# ProDocument_N64_SpyDVI_QSB_2024-08-22.net
KiCad netlist of a schematic drawn in EasyEDA Pro
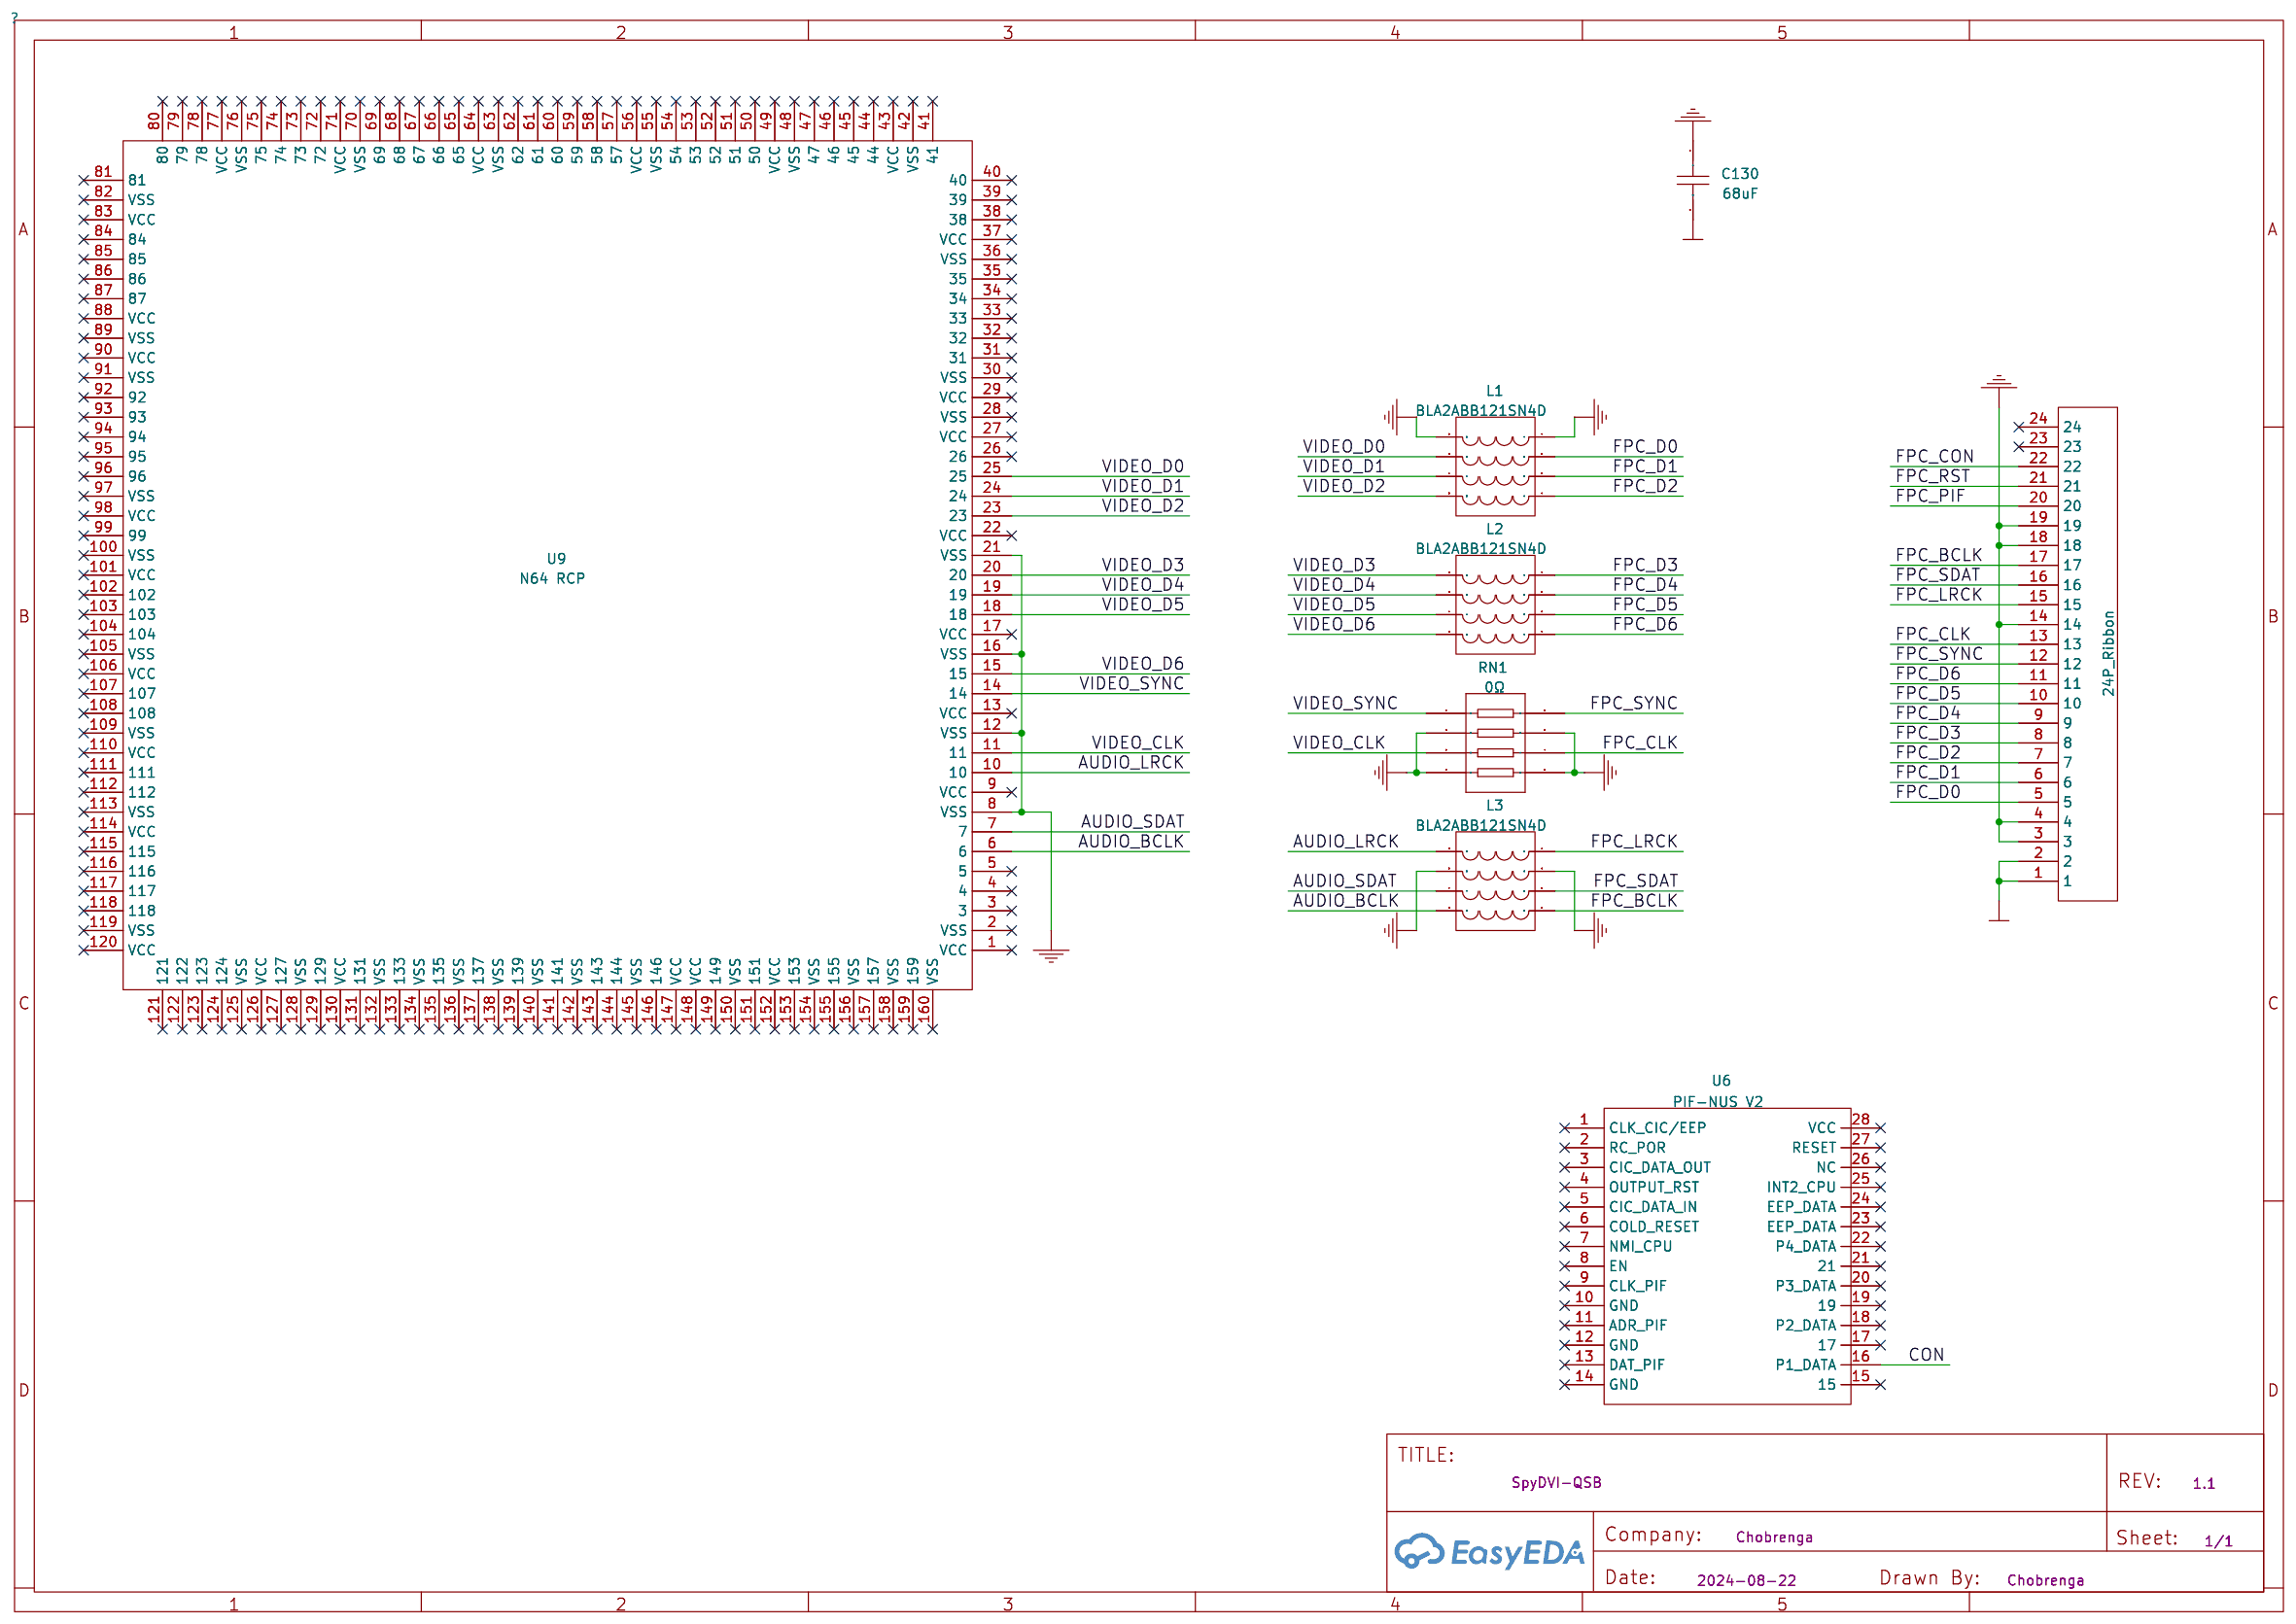
[diagram p0: schematic sheet]

(export (version "E")
  (design (tool "Eeschema 10.0.6"))
  (components
    (comp (ref "C130") (value "68uF") (libsource (lib "easyedapro") (part "68uF")))
    (comp (ref "L1")
      (value "BLA2ABB121SN4D")
      (footprint "easyedapro:BEAD-SMD_8P-L2.0-W1.0-P0.50-TL")
      (fields (field (name "Manufacturer") "muRata(村田)"))
      (libsource (lib "easyedapro") (part "BLA2ABB121SN4D"))
    )
    (comp (ref "L2")
      (value "BLA2ABB121SN4D")
      (footprint "easyedapro:BEAD-SMD_8P-L2.0-W1.0-P0.50-TL")
      (fields (field (name "Manufacturer") "muRata(村田)"))
      (libsource (lib "easyedapro") (part "BLA2ABB121SN4D"))
    )
    (comp (ref "L3")
      (value "BLA2ABB121SN4D")
      (footprint "easyedapro:BEAD-SMD_8P-L2.0-W1.0-P0.50-TL")
      (fields (field (name "Manufacturer") "muRata(村田)"))
      (libsource (lib "easyedapro") (part "BLA2ABB121SN4D"))
    )
    (comp (ref "RN1")
      (value "0Ω")
      (footprint "easyedapro:RES-ARRAY-SMD_0402-8P-L2.0-W1.0-BL")
      (fields (field (name "Manufacturer Part") "RC-MT08W000JT") (field (name "Manufacturer") "FH(风华)"))
      (libsource (lib "easyedapro") (part "0Ω"))
    )
    (comp (ref "U1")
      (value "24P_Ribbon")
      (footprint "easyedapro:24P_FFC")
      (libsource (lib "easyedapro") (part "24P_Ribbon"))
    )
    (comp (ref "U6") (value "PIF-NUS V2") (libsource (lib "easyedapro") (part "PIF-NUS V2")))
    (comp (ref "U9")
      (value "N64 RCP")
      (footprint "easyedapro:RCP NUS")
      (libsource (lib "easyedapro") (part "N64 RCP"))
    )
  )
  (nets
    (net (code "1") (name "+5V") (class "Default")
      (node (ref "C130") (pin "2") (pinfunction "2_2") (pintype "unspecified"))
      (node (ref "U1") (pin "1") (pinfunction "1_1") (pintype "unspecified"))
      (node (ref "U1") (pin "2") (pinfunction "2_2") (pintype "unspecified"))
    )
    (net (code "2") (name "/AUDIO_BCLK") (class "Default")
      (node (ref "L3") (pin "8") (pinfunction "8_8") (pintype "unspecified"))
      (node (ref "U9") (pin "6") (pinfunction "6_6") (pintype "unspecified"))
    )
    (net (code "3") (name "/AUDIO_LRCK") (class "Default")
      (node (ref "L3") (pin "5") (pinfunction "5_5") (pintype "unspecified"))
      (node (ref "U9") (pin "10") (pinfunction "10_10") (pintype "unspecified"))
    )
    (net (code "4") (name "/AUDIO_SDAT") (class "Default")
      (node (ref "L3") (pin "7") (pinfunction "7_7") (pintype "unspecified"))
      (node (ref "U9") (pin "7") (pinfunction "7_7") (pintype "unspecified"))
    )
    (net (code "5") (name "/CON") (class "Default")
      (node (ref "U6") (pin "16") (pinfunction "P1_DATA_16") (pintype "unspecified"))
    )
    (net (code "6") (name "/FPC_BCLK") (class "Default")
      (node (ref "L3") (pin "1") (pinfunction "1_1") (pintype "unspecified"))
      (node (ref "U1") (pin "17") (pinfunction "17_17") (pintype "unspecified"))
    )
    (net (code "7") (name "/FPC_CLK") (class "Default")
      (node (ref "RN1") (pin "7") (pinfunction "7_7") (pintype "input"))
      (node (ref "U1") (pin "13") (pinfunction "13_13") (pintype "unspecified"))
    )
    (net (code "8") (name "/FPC_CON") (class "Default")
      (node (ref "U1") (pin "22") (pinfunction "22_22") (pintype "unspecified"))
    )
    (net (code "9") (name "/FPC_D0") (class "Default")
      (node (ref "L1") (pin "3") (pinfunction "3_3") (pintype "unspecified"))
      (node (ref "U1") (pin "5") (pinfunction "5_5") (pintype "unspecified"))
    )
    (net (code "10") (name "/FPC_D1") (class "Default")
      (node (ref "L1") (pin "2") (pinfunction "2_2") (pintype "unspecified"))
      (node (ref "U1") (pin "6") (pinfunction "6_6") (pintype "unspecified"))
    )
    (net (code "11") (name "/FPC_D2") (class "Default")
      (node (ref "L1") (pin "1") (pinfunction "1_1") (pintype "unspecified"))
      (node (ref "U1") (pin "7") (pinfunction "7_7") (pintype "unspecified"))
    )
    (net (code "12") (name "/FPC_D3") (class "Default")
      (node (ref "L2") (pin "4") (pinfunction "4_4") (pintype "unspecified"))
      (node (ref "U1") (pin "8") (pinfunction "8_8") (pintype "unspecified"))
    )
    (net (code "13") (name "/FPC_D4") (class "Default")
      (node (ref "L2") (pin "3") (pinfunction "3_3") (pintype "unspecified"))
      (node (ref "U1") (pin "9") (pinfunction "9_9") (pintype "unspecified"))
    )
    (net (code "14") (name "/FPC_D5") (class "Default")
      (node (ref "L2") (pin "2") (pinfunction "2_2") (pintype "unspecified"))
      (node (ref "U1") (pin "10") (pinfunction "10_10") (pintype "unspecified"))
    )
    (net (code "15") (name "/FPC_D6") (class "Default")
      (node (ref "L2") (pin "1") (pinfunction "1_1") (pintype "unspecified"))
      (node (ref "U1") (pin "11") (pinfunction "11_11") (pintype "unspecified"))
    )
    (net (code "16") (name "/FPC_LRCK") (class "Default")
      (node (ref "L3") (pin "4") (pinfunction "4_4") (pintype "unspecified"))
      (node (ref "U1") (pin "15") (pinfunction "15_15") (pintype "unspecified"))
    )
    (net (code "17") (name "/FPC_PIF") (class "Default")
      (node (ref "U1") (pin "20") (pinfunction "20_20") (pintype "unspecified"))
    )
    (net (code "18") (name "/FPC_RST") (class "Default")
      (node (ref "U1") (pin "21") (pinfunction "21_21") (pintype "unspecified"))
    )
    (net (code "19") (name "/FPC_SDAT") (class "Default")
      (node (ref "L3") (pin "2") (pinfunction "2_2") (pintype "unspecified"))
      (node (ref "U1") (pin "16") (pinfunction "16_16") (pintype "unspecified"))
    )
    (net (code "20") (name "/FPC_SYNC") (class "Default")
      (node (ref "RN1") (pin "5") (pinfunction "5_5") (pintype "input"))
      (node (ref "U1") (pin "12") (pinfunction "12_12") (pintype "unspecified"))
    )
    (net (code "21") (name "/VIDEO_CLK") (class "Default")
      (node (ref "RN1") (pin "2") (pinfunction "2_2") (pintype "input"))
      (node (ref "U9") (pin "11") (pinfunction "11_11") (pintype "unspecified"))
    )
    (net (code "22") (name "/VIDEO_D0") (class "Default")
      (node (ref "L1") (pin "6") (pinfunction "6_6") (pintype "unspecified"))
      (node (ref "U9") (pin "25") (pinfunction "25_25") (pintype "unspecified"))
    )
    (net (code "23") (name "/VIDEO_D1") (class "Default")
      (node (ref "L1") (pin "7") (pinfunction "7_7") (pintype "unspecified"))
      (node (ref "U9") (pin "24") (pinfunction "24_24") (pintype "unspecified"))
    )
    (net (code "24") (name "/VIDEO_D2") (class "Default")
      (node (ref "L1") (pin "8") (pinfunction "8_8") (pintype "unspecified"))
      (node (ref "U9") (pin "23") (pinfunction "23_23") (pintype "unspecified"))
    )
    (net (code "25") (name "/VIDEO_D3") (class "Default")
      (node (ref "L2") (pin "5") (pinfunction "5_5") (pintype "unspecified"))
      (node (ref "U9") (pin "20") (pinfunction "20_20") (pintype "unspecified"))
    )
    (net (code "26") (name "/VIDEO_D4") (class "Default")
      (node (ref "L2") (pin "6") (pinfunction "6_6") (pintype "unspecified"))
      (node (ref "U9") (pin "19") (pinfunction "19_19") (pintype "unspecified"))
    )
    (net (code "27") (name "/VIDEO_D5") (class "Default")
      (node (ref "L2") (pin "7") (pinfunction "7_7") (pintype "unspecified"))
      (node (ref "U9") (pin "18") (pinfunction "18_18") (pintype "unspecified"))
    )
    (net (code "28") (name "/VIDEO_D6") (class "Default")
      (node (ref "L2") (pin "8") (pinfunction "8_8") (pintype "unspecified"))
      (node (ref "U9") (pin "15") (pinfunction "15_15") (pintype "unspecified"))
    )
    (net (code "29") (name "/VIDEO_SYNC") (class "Default")
      (node (ref "RN1") (pin "4") (pinfunction "4_4") (pintype "input"))
      (node (ref "U9") (pin "14") (pinfunction "14_14") (pintype "unspecified"))
    )
    (net (code "30") (name "GND") (class "Default")
      (node (ref "C130") (pin "1") (pinfunction "1_1") (pintype "unspecified"))
      (node (ref "L1") (pin "4") (pinfunction "4_4") (pintype "unspecified"))
      (node (ref "L1") (pin "5") (pinfunction "5_5") (pintype "unspecified"))
      (node (ref "L3") (pin "3") (pinfunction "3_3") (pintype "unspecified"))
      (node (ref "L3") (pin "6") (pinfunction "6_6") (pintype "unspecified"))
      (node (ref "RN1") (pin "1") (pinfunction "1_1") (pintype "input"))
      (node (ref "RN1") (pin "3") (pinfunction "3_3") (pintype "input"))
      (node (ref "RN1") (pin "6") (pinfunction "6_6") (pintype "input"))
      (node (ref "RN1") (pin "8") (pinfunction "8_8") (pintype "input"))
      (node (ref "U1") (pin "14") (pinfunction "14_14") (pintype "unspecified"))
      (node (ref "U1") (pin "18") (pinfunction "18_18") (pintype "unspecified"))
      (node (ref "U1") (pin "19") (pinfunction "19_19") (pintype "unspecified"))
      (node (ref "U1") (pin "3") (pinfunction "3_3") (pintype "unspecified"))
      (node (ref "U1") (pin "4") (pinfunction "4_4") (pintype "unspecified"))
      (node (ref "U9") (pin "12") (pinfunction "VSS_12") (pintype "unspecified"))
      (node (ref "U9") (pin "16") (pinfunction "VSS_16") (pintype "unspecified"))
      (node (ref "U9") (pin "21") (pinfunction "VSS_21") (pintype "unspecified"))
      (node (ref "U9") (pin "8") (pinfunction "VSS_8") (pintype "unspecified"))
    )
    (net (code "31") (name "unconnected-(U1-Pad23)") (class "Default")
      (node (ref "U1") (pin "23") (pinfunction "23_23") (pintype "unspecified+no_connect"))
    )
    (net (code "32") (name "unconnected-(U1-Pad24)") (class "Default")
      (node (ref "U1") (pin "24") (pinfunction "24_24") (pintype "unspecified+no_connect"))
    )
    (net (code "33") (name "unconnected-(U6-ADR_PIF-Pad11)") (class "Default")
      (node (ref "U6") (pin "11") (pinfunction "ADR_PIF_11") (pintype "unspecified+no_connect"))
    )
    (net (code "34") (name "unconnected-(U6-CIC_DATA_IN-Pad5)") (class "Default")
      (node (ref "U6") (pin "5") (pinfunction "CIC_DATA_IN_5") (pintype "unspecified+no_connect"))
    )
    (net (code "35") (name "unconnected-(U6-CIC_DATA_OUT-Pad3)") (class "Default")
      (node (ref "U6") (pin "3") (pinfunction "CIC_DATA_OUT_3") (pintype "unspecified+no_connect"))
    )
    (net (code "36") (name "unconnected-(U6-CLK_CIC{slash}EEP-Pad1)") (class "Default")
      (node (ref "U6") (pin "1") (pinfunction "CLK_CIC/EEP_1") (pintype "unspecified+no_connect"))
    )
    (net (code "37") (name "unconnected-(U6-CLK_PIF-Pad9)") (class "Default")
      (node (ref "U6") (pin "9") (pinfunction "CLK_PIF_9") (pintype "unspecified+no_connect"))
    )
    (net (code "38") (name "unconnected-(U6-COLD_RESET-Pad6)") (class "Default")
      (node (ref "U6") (pin "6") (pinfunction "COLD_RESET_6") (pintype "unspecified+no_connect"))
    )
    (net (code "39") (name "unconnected-(U6-DAT_PIF-Pad13)") (class "Default")
      (node (ref "U6") (pin "13") (pinfunction "DAT_PIF_13") (pintype "unspecified+no_connect"))
    )
    (net (code "40") (name "unconnected-(U6-EEP_DATA-Pad23)") (class "Default")
      (node (ref "U6") (pin "23") (pinfunction "EEP_DATA_23") (pintype "unspecified+no_connect"))
    )
    (net (code "41") (name "unconnected-(U6-EEP_DATA-Pad24)") (class "Default")
      (node (ref "U6") (pin "24") (pinfunction "EEP_DATA_24") (pintype "unspecified+no_connect"))
    )
    (net (code "42") (name "unconnected-(U6-EN-Pad8)") (class "Default")
      (node (ref "U6") (pin "8") (pinfunction "EN_8") (pintype "unspecified+no_connect"))
    )
    (net (code "43") (name "unconnected-(U6-GND-Pad10)") (class "Default")
      (node (ref "U6") (pin "10") (pinfunction "GND_10") (pintype "unspecified+no_connect"))
    )
    (net (code "44") (name "unconnected-(U6-GND-Pad12)") (class "Default")
      (node (ref "U6") (pin "12") (pinfunction "GND_12") (pintype "unspecified+no_connect"))
    )
    (net (code "45") (name "unconnected-(U6-GND-Pad14)") (class "Default")
      (node (ref "U6") (pin "14") (pinfunction "GND_14") (pintype "unspecified+no_connect"))
    )
    (net (code "46") (name "unconnected-(U6-INT2_CPU-Pad25)") (class "Default")
      (node (ref "U6") (pin "25") (pinfunction "INT2_CPU_25") (pintype "unspecified+no_connect"))
    )
    (net (code "47") (name "unconnected-(U6-NC-Pad26)") (class "Default")
      (node (ref "U6") (pin "26") (pinfunction "NC_26") (pintype "unspecified+no_connect"))
    )
    (net (code "48") (name "unconnected-(U6-NMI_CPU-Pad7)") (class "Default")
      (node (ref "U6") (pin "7") (pinfunction "NMI_CPU_7") (pintype "unspecified+no_connect"))
    )
    (net (code "49") (name "unconnected-(U6-OUTPUT_RST-Pad4)") (class "Default")
      (node (ref "U6") (pin "4") (pinfunction "OUTPUT_RST_4") (pintype "unspecified+no_connect"))
    )
    (net (code "50") (name "unconnected-(U6-P2_DATA-Pad18)") (class "Default")
      (node (ref "U6") (pin "18") (pinfunction "P2_DATA_18") (pintype "unspecified+no_connect"))
    )
    (net (code "51") (name "unconnected-(U6-P3_DATA-Pad20)") (class "Default")
      (node (ref "U6") (pin "20") (pinfunction "P3_DATA_20") (pintype "unspecified+no_connect"))
    )
    (net (code "52") (name "unconnected-(U6-P4_DATA-Pad22)") (class "Default")
      (node (ref "U6") (pin "22") (pinfunction "P4_DATA_22") (pintype "unspecified+no_connect"))
    )
    (net (code "53") (name "unconnected-(U6-Pad15)") (class "Default")
      (node (ref "U6") (pin "15") (pinfunction "15_15") (pintype "unspecified+no_connect"))
    )
    (net (code "54") (name "unconnected-(U6-Pad17)") (class "Default")
      (node (ref "U6") (pin "17") (pinfunction "17_17") (pintype "unspecified+no_connect"))
    )
    (net (code "55") (name "unconnected-(U6-Pad19)") (class "Default")
      (node (ref "U6") (pin "19") (pinfunction "19_19") (pintype "unspecified+no_connect"))
    )
    (net (code "56") (name "unconnected-(U6-Pad21)") (class "Default")
      (node (ref "U6") (pin "21") (pinfunction "21_21") (pintype "unspecified+no_connect"))
    )
    (net (code "57") (name "unconnected-(U6-RC_POR-Pad2)") (class "Default")
      (node (ref "U6") (pin "2") (pinfunction "RC_POR_2") (pintype "unspecified+no_connect"))
    )
    (net (code "58") (name "unconnected-(U6-RESET-Pad27)") (class "Default")
      (node (ref "U6") (pin "27") (pinfunction "RESET_27") (pintype "unspecified+no_connect"))
    )
    (net (code "59") (name "unconnected-(U6-VCC-Pad28)") (class "Default")
      (node (ref "U6") (pin "28") (pinfunction "VCC_28") (pintype "unspecified+no_connect"))
    )
    (net (code "60") (name "unconnected-(U9-Pad3)") (class "Default")
      (node (ref "U9") (pin "3") (pinfunction "3_3") (pintype "unspecified+no_connect"))
    )
    (net (code "61") (name "unconnected-(U9-Pad4)") (class "Default")
      (node (ref "U9") (pin "4") (pinfunction "4_4") (pintype "unspecified+no_connect"))
    )
    (net (code "62") (name "unconnected-(U9-Pad5)") (class "Default")
      (node (ref "U9") (pin "5") (pinfunction "5_5") (pintype "unspecified+no_connect"))
    )
    (net (code "63") (name "unconnected-(U9-Pad26)") (class "Default")
      (node (ref "U9") (pin "26") (pinfunction "26_26") (pintype "unspecified+no_connect"))
    )
    (net (code "64") (name "unconnected-(U9-Pad31)") (class "Default")
      (node (ref "U9") (pin "31") (pinfunction "31_31") (pintype "unspecified+no_connect"))
    )
    (net (code "65") (name "unconnected-(U9-Pad32)") (class "Default")
      (node (ref "U9") (pin "32") (pinfunction "32_32") (pintype "unspecified+no_connect"))
    )
    (net (code "66") (name "unconnected-(U9-Pad33)") (class "Default")
      (node (ref "U9") (pin "33") (pinfunction "33_33") (pintype "unspecified+no_connect"))
    )
    (net (code "67") (name "unconnected-(U9-Pad34)") (class "Default")
      (node (ref "U9") (pin "34") (pinfunction "34_34") (pintype "unspecified+no_connect"))
    )
    (net (code "68") (name "unconnected-(U9-Pad35)") (class "Default")
      (node (ref "U9") (pin "35") (pinfunction "35_35") (pintype "unspecified+no_connect"))
    )
    (net (code "69") (name "unconnected-(U9-Pad38)") (class "Default")
      (node (ref "U9") (pin "38") (pinfunction "38_38") (pintype "unspecified+no_connect"))
    )
    (net (code "70") (name "unconnected-(U9-Pad39)") (class "Default")
      (node (ref "U9") (pin "39") (pinfunction "39_39") (pintype "unspecified+no_connect"))
    )
    (net (code "71") (name "unconnected-(U9-Pad40)") (class "Default")
      (node (ref "U9") (pin "40") (pinfunction "40_40") (pintype "unspecified+no_connect"))
    )
    (net (code "72") (name "unconnected-(U9-Pad41)") (class "Default")
      (node (ref "U9") (pin "41") (pinfunction "41_41") (pintype "unspecified+no_connect"))
    )
    (net (code "73") (name "unconnected-(U9-Pad44)") (class "Default")
      (node (ref "U9") (pin "44") (pinfunction "44_44") (pintype "unspecified+no_connect"))
    )
    (net (code "74") (name "unconnected-(U9-Pad45)") (class "Default")
      (node (ref "U9") (pin "45") (pinfunction "45_45") (pintype "unspecified+no_connect"))
    )
    (net (code "75") (name "unconnected-(U9-Pad46)") (class "Default")
      (node (ref "U9") (pin "46") (pinfunction "46_46") (pintype "unspecified+no_connect"))
    )
    (net (code "76") (name "unconnected-(U9-Pad47)") (class "Default")
      (node (ref "U9") (pin "47") (pinfunction "47_47") (pintype "unspecified+no_connect"))
    )
    (net (code "77") (name "unconnected-(U9-Pad50)") (class "Default")
      (node (ref "U9") (pin "50") (pinfunction "50_50") (pintype "unspecified+no_connect"))
    )
    (net (code "78") (name "unconnected-(U9-Pad51)") (class "Default")
      (node (ref "U9") (pin "51") (pinfunction "51_51") (pintype "unspecified+no_connect"))
    )
    (net (code "79") (name "unconnected-(U9-Pad52)") (class "Default")
      (node (ref "U9") (pin "52") (pinfunction "52_52") (pintype "unspecified+no_connect"))
    )
    (net (code "80") (name "unconnected-(U9-Pad53)") (class "Default")
      (node (ref "U9") (pin "53") (pinfunction "53_53") (pintype "unspecified+no_connect"))
    )
    (net (code "81") (name "unconnected-(U9-Pad54)") (class "Default")
      (node (ref "U9") (pin "54") (pinfunction "54_54") (pintype "unspecified+no_connect"))
    )
    (net (code "82") (name "unconnected-(U9-Pad57)") (class "Default")
      (node (ref "U9") (pin "57") (pinfunction "57_57") (pintype "unspecified+no_connect"))
    )
    (net (code "83") (name "unconnected-(U9-Pad58)") (class "Default")
      (node (ref "U9") (pin "58") (pinfunction "58_58") (pintype "unspecified+no_connect"))
    )
    (net (code "84") (name "unconnected-(U9-Pad59)") (class "Default")
      (node (ref "U9") (pin "59") (pinfunction "59_59") (pintype "unspecified+no_connect"))
    )
    (net (code "85") (name "unconnected-(U9-Pad60)") (class "Default")
      (node (ref "U9") (pin "60") (pinfunction "60_60") (pintype "unspecified+no_connect"))
    )
    (net (code "86") (name "unconnected-(U9-Pad61)") (class "Default")
      (node (ref "U9") (pin "61") (pinfunction "61_61") (pintype "unspecified+no_connect"))
    )
    (net (code "87") (name "unconnected-(U9-Pad62)") (class "Default")
      (node (ref "U9") (pin "62") (pinfunction "62_62") (pintype "unspecified+no_connect"))
    )
    (net (code "88") (name "unconnected-(U9-Pad65)") (class "Default")
      (node (ref "U9") (pin "65") (pinfunction "65_65") (pintype "unspecified+no_connect"))
    )
    (net (code "89") (name "unconnected-(U9-Pad66)") (class "Default")
      (node (ref "U9") (pin "66") (pinfunction "66_66") (pintype "unspecified+no_connect"))
    )
    (net (code "90") (name "unconnected-(U9-Pad67)") (class "Default")
      (node (ref "U9") (pin "67") (pinfunction "67_67") (pintype "unspecified+no_connect"))
    )
    (net (code "91") (name "unconnected-(U9-Pad68)") (class "Default")
      (node (ref "U9") (pin "68") (pinfunction "68_68") (pintype "unspecified+no_connect"))
    )
    (net (code "92") (name "unconnected-(U9-Pad69)") (class "Default")
      (node (ref "U9") (pin "69") (pinfunction "69_69") (pintype "unspecified+no_connect"))
    )
    (net (code "93") (name "unconnected-(U9-Pad72)") (class "Default")
      (node (ref "U9") (pin "72") (pinfunction "72_72") (pintype "unspecified+no_connect"))
    )
    (net (code "94") (name "unconnected-(U9-Pad73)") (class "Default")
      (node (ref "U9") (pin "73") (pinfunction "73_73") (pintype "unspecified+no_connect"))
    )
    (net (code "95") (name "unconnected-(U9-Pad74)") (class "Default")
      (node (ref "U9") (pin "74") (pinfunction "74_74") (pintype "unspecified+no_connect"))
    )
    (net (code "96") (name "unconnected-(U9-Pad75)") (class "Default")
      (node (ref "U9") (pin "75") (pinfunction "75_75") (pintype "unspecified+no_connect"))
    )
    (net (code "97") (name "unconnected-(U9-Pad78)") (class "Default")
      (node (ref "U9") (pin "78") (pinfunction "78_78") (pintype "unspecified+no_connect"))
    )
    (net (code "98") (name "unconnected-(U9-Pad79)") (class "Default")
      (node (ref "U9") (pin "79") (pinfunction "79_79") (pintype "unspecified+no_connect"))
    )
    (net (code "99") (name "unconnected-(U9-Pad80)") (class "Default")
      (node (ref "U9") (pin "80") (pinfunction "80_80") (pintype "unspecified+no_connect"))
    )
    (net (code "100") (name "unconnected-(U9-Pad81)") (class "Default")
      (node (ref "U9") (pin "81") (pinfunction "81_81") (pintype "unspecified+no_connect"))
    )
    (net (code "101") (name "unconnected-(U9-Pad84)") (class "Default")
      (node (ref "U9") (pin "84") (pinfunction "84_84") (pintype "unspecified+no_connect"))
    )
    (net (code "102") (name "unconnected-(U9-Pad85)") (class "Default")
      (node (ref "U9") (pin "85") (pinfunction "85_85") (pintype "unspecified+no_connect"))
    )
    (net (code "103") (name "unconnected-(U9-Pad86)") (class "Default")
      (node (ref "U9") (pin "86") (pinfunction "86_86") (pintype "unspecified+no_connect"))
    )
    (net (code "104") (name "unconnected-(U9-Pad87)") (class "Default")
      (node (ref "U9") (pin "87") (pinfunction "87_87") (pintype "unspecified+no_connect"))
    )
    (net (code "105") (name "unconnected-(U9-Pad92)") (class "Default")
      (node (ref "U9") (pin "92") (pinfunction "92_92") (pintype "unspecified+no_connect"))
    )
    (net (code "106") (name "unconnected-(U9-Pad93)") (class "Default")
      (node (ref "U9") (pin "93") (pinfunction "93_93") (pintype "unspecified+no_connect"))
    )
    (net (code "107") (name "unconnected-(U9-Pad94)") (class "Default")
      (node (ref "U9") (pin "94") (pinfunction "94_94") (pintype "unspecified+no_connect"))
    )
    (net (code "108") (name "unconnected-(U9-Pad95)") (class "Default")
      (node (ref "U9") (pin "95") (pinfunction "95_95") (pintype "unspecified+no_connect"))
    )
    (net (code "109") (name "unconnected-(U9-Pad96)") (class "Default")
      (node (ref "U9") (pin "96") (pinfunction "96_96") (pintype "unspecified+no_connect"))
    )
    (net (code "110") (name "unconnected-(U9-Pad99)") (class "Default")
      (node (ref "U9") (pin "99") (pinfunction "99_99") (pintype "unspecified+no_connect"))
    )
    (net (code "111") (name "unconnected-(U9-Pad102)") (class "Default")
      (node (ref "U9") (pin "102") (pinfunction "102_102") (pintype "unspecified+no_connect"))
    )
    (net (code "112") (name "unconnected-(U9-Pad103)") (class "Default")
      (node (ref "U9") (pin "103") (pinfunction "103_103") (pintype "unspecified+no_connect"))
    )
    (net (code "113") (name "unconnected-(U9-Pad104)") (class "Default")
      (node (ref "U9") (pin "104") (pinfunction "104_104") (pintype "unspecified+no_connect"))
    )
    (net (code "114") (name "unconnected-(U9-Pad107)") (class "Default")
      (node (ref "U9") (pin "107") (pinfunction "107_107") (pintype "unspecified+no_connect"))
    )
    (net (code "115") (name "unconnected-(U9-Pad108)") (class "Default")
      (node (ref "U9") (pin "108") (pinfunction "108_108") (pintype "unspecified+no_connect"))
    )
    (net (code "116") (name "unconnected-(U9-Pad111)") (class "Default")
      (node (ref "U9") (pin "111") (pinfunction "111_111") (pintype "unspecified+no_connect"))
    )
    (net (code "117") (name "unconnected-(U9-Pad112)") (class "Default")
      (node (ref "U9") (pin "112") (pinfunction "112_112") (pintype "unspecified+no_connect"))
    )
    (net (code "118") (name "unconnected-(U9-Pad115)") (class "Default")
      (node (ref "U9") (pin "115") (pinfunction "115_115") (pintype "unspecified+no_connect"))
    )
    (net (code "119") (name "unconnected-(U9-Pad116)") (class "Default")
      (node (ref "U9") (pin "116") (pinfunction "116_116") (pintype "unspecified+no_connect"))
    )
    (net (code "120") (name "unconnected-(U9-Pad117)") (class "Default")
      (node (ref "U9") (pin "117") (pinfunction "117_117") (pintype "unspecified+no_connect"))
    )
    (net (code "121") (name "unconnected-(U9-Pad118)") (class "Default")
      (node (ref "U9") (pin "118") (pinfunction "118_118") (pintype "unspecified+no_connect"))
    )
    (net (code "122") (name "unconnected-(U9-Pad121)") (class "Default")
      (node (ref "U9") (pin "121") (pinfunction "121_121") (pintype "unspecified+no_connect"))
    )
    (net (code "123") (name "unconnected-(U9-Pad122)") (class "Default")
      (node (ref "U9") (pin "122") (pinfunction "122_122") (pintype "unspecified+no_connect"))
    )
    (net (code "124") (name "unconnected-(U9-Pad123)") (class "Default")
      (node (ref "U9") (pin "123") (pinfunction "123_123") (pintype "unspecified+no_connect"))
    )
    (net (code "125") (name "unconnected-(U9-Pad124)") (class "Default")
      (node (ref "U9") (pin "124") (pinfunction "124_124") (pintype "unspecified+no_connect"))
    )
    (net (code "126") (name "unconnected-(U9-Pad127)") (class "Default")
      (node (ref "U9") (pin "127") (pinfunction "127_127") (pintype "unspecified+no_connect"))
    )
    (net (code "127") (name "unconnected-(U9-Pad129)") (class "Default")
      (node (ref "U9") (pin "129") (pinfunction "129_129") (pintype "unspecified+no_connect"))
    )
    (net (code "128") (name "unconnected-(U9-Pad131)") (class "Default")
      (node (ref "U9") (pin "131") (pinfunction "131_131") (pintype "unspecified+no_connect"))
    )
    (net (code "129") (name "unconnected-(U9-Pad133)") (class "Default")
      (node (ref "U9") (pin "133") (pinfunction "133_133") (pintype "unspecified+no_connect"))
    )
    (net (code "130") (name "unconnected-(U9-Pad135)") (class "Default")
      (node (ref "U9") (pin "135") (pinfunction "135_135") (pintype "unspecified+no_connect"))
    )
    (net (code "131") (name "unconnected-(U9-Pad137)") (class "Default")
      (node (ref "U9") (pin "137") (pinfunction "137_137") (pintype "unspecified+no_connect"))
    )
    (net (code "132") (name "unconnected-(U9-Pad139)") (class "Default")
      (node (ref "U9") (pin "139") (pinfunction "139_139") (pintype "unspecified+no_connect"))
    )
    (net (code "133") (name "unconnected-(U9-Pad141)") (class "Default")
      (node (ref "U9") (pin "141") (pinfunction "141_141") (pintype "unspecified+no_connect"))
    )
    (net (code "134") (name "unconnected-(U9-Pad143)") (class "Default")
      (node (ref "U9") (pin "143") (pinfunction "143_143") (pintype "unspecified+no_connect"))
    )
    (net (code "135") (name "unconnected-(U9-Pad144)") (class "Default")
      (node (ref "U9") (pin "144") (pinfunction "144_144") (pintype "unspecified+no_connect"))
    )
    (net (code "136") (name "unconnected-(U9-Pad146)") (class "Default")
      (node (ref "U9") (pin "146") (pinfunction "146_146") (pintype "unspecified+no_connect"))
    )
    (net (code "137") (name "unconnected-(U9-Pad149)") (class "Default")
      (node (ref "U9") (pin "149") (pinfunction "149_149") (pintype "unspecified+no_connect"))
    )
    (net (code "138") (name "unconnected-(U9-Pad151)") (class "Default")
      (node (ref "U9") (pin "151") (pinfunction "151_151") (pintype "unspecified+no_connect"))
    )
    (net (code "139") (name "unconnected-(U9-Pad153)") (class "Default")
      (node (ref "U9") (pin "153") (pinfunction "153_153") (pintype "unspecified+no_connect"))
    )
    (net (code "140") (name "unconnected-(U9-Pad155)") (class "Default")
      (node (ref "U9") (pin "155") (pinfunction "155_155") (pintype "unspecified+no_connect"))
    )
    (net (code "141") (name "unconnected-(U9-Pad157)") (class "Default")
      (node (ref "U9") (pin "157") (pinfunction "157_157") (pintype "unspecified+no_connect"))
    )
    (net (code "142") (name "unconnected-(U9-Pad159)") (class "Default")
      (node (ref "U9") (pin "159") (pinfunction "159_159") (pintype "unspecified+no_connect"))
    )
    (net (code "143") (name "unconnected-(U9-VCC-Pad1)") (class "Default")
      (node (ref "U9") (pin "1") (pinfunction "VCC_1") (pintype "unspecified+no_connect"))
    )
    (net (code "144") (name "unconnected-(U9-VCC-Pad9)") (class "Default")
      (node (ref "U9") (pin "9") (pinfunction "VCC_9") (pintype "unspecified+no_connect"))
    )
    (net (code "145") (name "unconnected-(U9-VCC-Pad13)") (class "Default")
      (node (ref "U9") (pin "13") (pinfunction "VCC_13") (pintype "unspecified+no_connect"))
    )
    (net (code "146") (name "unconnected-(U9-VCC-Pad17)") (class "Default")
      (node (ref "U9") (pin "17") (pinfunction "VCC_17") (pintype "unspecified+no_connect"))
    )
    (net (code "147") (name "unconnected-(U9-VCC-Pad22)") (class "Default")
      (node (ref "U9") (pin "22") (pinfunction "VCC_22") (pintype "unspecified+no_connect"))
    )
    (net (code "148") (name "unconnected-(U9-VCC-Pad27)") (class "Default")
      (node (ref "U9") (pin "27") (pinfunction "VCC_27") (pintype "unspecified+no_connect"))
    )
    (net (code "149") (name "unconnected-(U9-VCC-Pad29)") (class "Default")
      (node (ref "U9") (pin "29") (pinfunction "VCC_29") (pintype "unspecified+no_connect"))
    )
    (net (code "150") (name "unconnected-(U9-VCC-Pad37)") (class "Default")
      (node (ref "U9") (pin "37") (pinfunction "VCC_37") (pintype "unspecified+no_connect"))
    )
    (net (code "151") (name "unconnected-(U9-VCC-Pad43)") (class "Default")
      (node (ref "U9") (pin "43") (pinfunction "VCC_43") (pintype "unspecified+no_connect"))
    )
    (net (code "152") (name "unconnected-(U9-VCC-Pad49)") (class "Default")
      (node (ref "U9") (pin "49") (pinfunction "VCC_49") (pintype "unspecified+no_connect"))
    )
    (net (code "153") (name "unconnected-(U9-VCC-Pad56)") (class "Default")
      (node (ref "U9") (pin "56") (pinfunction "VCC_56") (pintype "unspecified+no_connect"))
    )
    (net (code "154") (name "unconnected-(U9-VCC-Pad64)") (class "Default")
      (node (ref "U9") (pin "64") (pinfunction "VCC_64") (pintype "unspecified+no_connect"))
    )
    (net (code "155") (name "unconnected-(U9-VCC-Pad71)") (class "Default")
      (node (ref "U9") (pin "71") (pinfunction "VCC_71") (pintype "unspecified+no_connect"))
    )
    (net (code "156") (name "unconnected-(U9-VCC-Pad77)") (class "Default")
      (node (ref "U9") (pin "77") (pinfunction "VCC_77") (pintype "unspecified+no_connect"))
    )
    (net (code "157") (name "unconnected-(U9-VCC-Pad83)") (class "Default")
      (node (ref "U9") (pin "83") (pinfunction "VCC_83") (pintype "unspecified+no_connect"))
    )
    (net (code "158") (name "unconnected-(U9-VCC-Pad88)") (class "Default")
      (node (ref "U9") (pin "88") (pinfunction "VCC_88") (pintype "unspecified+no_connect"))
    )
    (net (code "159") (name "unconnected-(U9-VCC-Pad90)") (class "Default")
      (node (ref "U9") (pin "90") (pinfunction "VCC_90") (pintype "unspecified+no_connect"))
    )
    (net (code "160") (name "unconnected-(U9-VCC-Pad98)") (class "Default")
      (node (ref "U9") (pin "98") (pinfunction "VCC_98") (pintype "unspecified+no_connect"))
    )
    (net (code "161") (name "unconnected-(U9-VCC-Pad101)") (class "Default")
      (node (ref "U9") (pin "101") (pinfunction "VCC_101") (pintype "unspecified+no_connect"))
    )
    (net (code "162") (name "unconnected-(U9-VCC-Pad106)") (class "Default")
      (node (ref "U9") (pin "106") (pinfunction "VCC_106") (pintype "unspecified+no_connect"))
    )
    (net (code "163") (name "unconnected-(U9-VCC-Pad110)") (class "Default")
      (node (ref "U9") (pin "110") (pinfunction "VCC_110") (pintype "unspecified+no_connect"))
    )
    (net (code "164") (name "unconnected-(U9-VCC-Pad114)") (class "Default")
      (node (ref "U9") (pin "114") (pinfunction "VCC_114") (pintype "unspecified+no_connect"))
    )
    (net (code "165") (name "unconnected-(U9-VCC-Pad120)") (class "Default")
      (node (ref "U9") (pin "120") (pinfunction "VCC_120") (pintype "unspecified+no_connect"))
    )
    (net (code "166") (name "unconnected-(U9-VCC-Pad126)") (class "Default")
      (node (ref "U9") (pin "126") (pinfunction "VCC_126") (pintype "unspecified+no_connect"))
    )
    (net (code "167") (name "unconnected-(U9-VCC-Pad130)") (class "Default")
      (node (ref "U9") (pin "130") (pinfunction "VCC_130") (pintype "unspecified+no_connect"))
    )
    (net (code "168") (name "unconnected-(U9-VCC-Pad147)") (class "Default")
      (node (ref "U9") (pin "147") (pinfunction "VCC_147") (pintype "unspecified+no_connect"))
    )
    (net (code "169") (name "unconnected-(U9-VCC-Pad148)") (class "Default")
      (node (ref "U9") (pin "148") (pinfunction "VCC_148") (pintype "unspecified+no_connect"))
    )
    (net (code "170") (name "unconnected-(U9-VCC-Pad152)") (class "Default")
      (node (ref "U9") (pin "152") (pinfunction "VCC_152") (pintype "unspecified+no_connect"))
    )
    (net (code "171") (name "unconnected-(U9-VSS-Pad2)") (class "Default")
      (node (ref "U9") (pin "2") (pinfunction "VSS_2") (pintype "unspecified+no_connect"))
    )
    (net (code "172") (name "unconnected-(U9-VSS-Pad28)") (class "Default")
      (node (ref "U9") (pin "28") (pinfunction "VSS_28") (pintype "unspecified+no_connect"))
    )
    (net (code "173") (name "unconnected-(U9-VSS-Pad30)") (class "Default")
      (node (ref "U9") (pin "30") (pinfunction "VSS_30") (pintype "unspecified+no_connect"))
    )
    (net (code "174") (name "unconnected-(U9-VSS-Pad36)") (class "Default")
      (node (ref "U9") (pin "36") (pinfunction "VSS_36") (pintype "unspecified+no_connect"))
    )
    (net (code "175") (name "unconnected-(U9-VSS-Pad42)") (class "Default")
      (node (ref "U9") (pin "42") (pinfunction "VSS_42") (pintype "unspecified+no_connect"))
    )
    (net (code "176") (name "unconnected-(U9-VSS-Pad48)") (class "Default")
      (node (ref "U9") (pin "48") (pinfunction "VSS_48") (pintype "unspecified+no_connect"))
    )
    (net (code "177") (name "unconnected-(U9-VSS-Pad55)") (class "Default")
      (node (ref "U9") (pin "55") (pinfunction "VSS_55") (pintype "unspecified+no_connect"))
    )
    (net (code "178") (name "unconnected-(U9-VSS-Pad63)") (class "Default")
      (node (ref "U9") (pin "63") (pinfunction "VSS_63") (pintype "unspecified+no_connect"))
    )
    (net (code "179") (name "unconnected-(U9-VSS-Pad70)") (class "Default")
      (node (ref "U9") (pin "70") (pinfunction "VSS_70") (pintype "unspecified+no_connect"))
    )
    (net (code "180") (name "unconnected-(U9-VSS-Pad76)") (class "Default")
      (node (ref "U9") (pin "76") (pinfunction "VSS_76") (pintype "unspecified+no_connect"))
    )
    (net (code "181") (name "unconnected-(U9-VSS-Pad82)") (class "Default")
      (node (ref "U9") (pin "82") (pinfunction "VSS_82") (pintype "unspecified+no_connect"))
    )
    (net (code "182") (name "unconnected-(U9-VSS-Pad89)") (class "Default")
      (node (ref "U9") (pin "89") (pinfunction "VSS_89") (pintype "unspecified+no_connect"))
    )
    (net (code "183") (name "unconnected-(U9-VSS-Pad91)") (class "Default")
      (node (ref "U9") (pin "91") (pinfunction "VSS_91") (pintype "unspecified+no_connect"))
    )
    (net (code "184") (name "unconnected-(U9-VSS-Pad97)") (class "Default")
      (node (ref "U9") (pin "97") (pinfunction "VSS_97") (pintype "unspecified+no_connect"))
    )
    (net (code "185") (name "unconnected-(U9-VSS-Pad100)") (class "Default")
      (node (ref "U9") (pin "100") (pinfunction "VSS_100") (pintype "unspecified+no_connect"))
    )
    (net (code "186") (name "unconnected-(U9-VSS-Pad105)") (class "Default")
      (node (ref "U9") (pin "105") (pinfunction "VSS_105") (pintype "unspecified+no_connect"))
    )
    (net (code "187") (name "unconnected-(U9-VSS-Pad109)") (class "Default")
      (node (ref "U9") (pin "109") (pinfunction "VSS_109") (pintype "unspecified+no_connect"))
    )
    (net (code "188") (name "unconnected-(U9-VSS-Pad113)") (class "Default")
      (node (ref "U9") (pin "113") (pinfunction "VSS_113") (pintype "unspecified+no_connect"))
    )
    (net (code "189") (name "unconnected-(U9-VSS-Pad119)") (class "Default")
      (node (ref "U9") (pin "119") (pinfunction "VSS_119") (pintype "unspecified+no_connect"))
    )
    (net (code "190") (name "unconnected-(U9-VSS-Pad125)") (class "Default")
      (node (ref "U9") (pin "125") (pinfunction "VSS_125") (pintype "unspecified+no_connect"))
    )
    (net (code "191") (name "unconnected-(U9-VSS-Pad128)") (class "Default")
      (node (ref "U9") (pin "128") (pinfunction "VSS_128") (pintype "unspecified+no_connect"))
    )
    (net (code "192") (name "unconnected-(U9-VSS-Pad132)") (class "Default")
      (node (ref "U9") (pin "132") (pinfunction "VSS_132") (pintype "unspecified+no_connect"))
    )
    (net (code "193") (name "unconnected-(U9-VSS-Pad134)") (class "Default")
      (node (ref "U9") (pin "134") (pinfunction "VSS_134") (pintype "unspecified+no_connect"))
    )
    (net (code "194") (name "unconnected-(U9-VSS-Pad136)") (class "Default")
      (node (ref "U9") (pin "136") (pinfunction "VSS_136") (pintype "unspecified+no_connect"))
    )
    (net (code "195") (name "unconnected-(U9-VSS-Pad138)") (class "Default")
      (node (ref "U9") (pin "138") (pinfunction "VSS_138") (pintype "unspecified+no_connect"))
    )
    (net (code "196") (name "unconnected-(U9-VSS-Pad140)") (class "Default")
      (node (ref "U9") (pin "140") (pinfunction "VSS_140") (pintype "unspecified+no_connect"))
    )
    (net (code "197") (name "unconnected-(U9-VSS-Pad142)") (class "Default")
      (node (ref "U9") (pin "142") (pinfunction "VSS_142") (pintype "unspecified+no_connect"))
    )
    (net (code "198") (name "unconnected-(U9-VSS-Pad145)") (class "Default")
      (node (ref "U9") (pin "145") (pinfunction "VSS_145") (pintype "unspecified+no_connect"))
    )
    (net (code "199") (name "unconnected-(U9-VSS-Pad150)") (class "Default")
      (node (ref "U9") (pin "150") (pinfunction "VSS_150") (pintype "unspecified+no_connect"))
    )
    (net (code "200") (name "unconnected-(U9-VSS-Pad154)") (class "Default")
      (node (ref "U9") (pin "154") (pinfunction "VSS_154") (pintype "unspecified+no_connect"))
    )
    (net (code "201") (name "unconnected-(U9-VSS-Pad156)") (class "Default")
      (node (ref "U9") (pin "156") (pinfunction "VSS_156") (pintype "unspecified+no_connect"))
    )
    (net (code "202") (name "unconnected-(U9-VSS-Pad158)") (class "Default")
      (node (ref "U9") (pin "158") (pinfunction "VSS_158") (pintype "unspecified+no_connect"))
    )
    (net (code "203") (name "unconnected-(U9-VSS-Pad160)") (class "Default")
      (node (ref "U9") (pin "160") (pinfunction "VSS_160") (pintype "unspecified+no_connect"))
    )
  )
)
